# qinxie.net
KiCad netlist of a schematic drawn in Altium Designer
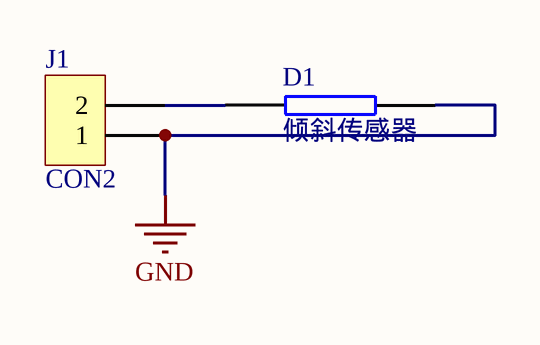
[diagram p0: qinxie.SchDoc]

(export (version "E")
  (design (tool "Eeschema 10.0.6"))
  (components
    (comp (ref "D1") (value "倾斜传感器") (footprint "倾斜传感器") (libsource (lib "AIWAC-bolsterV01") (part "R")))
    (comp (ref "J1")
      (value "CON2")
      (footprint "J-SH1.0-T-1-LT-2A")
      (description "Connector")
      (libsource (lib "AIWAC-bolsterV01") (part "CON2"))
    )
  )
  (nets
    (net (code "1") (name "GND") (class "Default")
      (node (ref "D1") (pin "2") (pinfunction "2_2") (pintype "passive"))
      (node (ref "J1") (pin "1") (pinfunction "1_1") (pintype "passive"))
    )
    (net (code "2") (name "Net-(D1-Pad1)") (class "Default")
      (node (ref "D1") (pin "1") (pinfunction "1_1") (pintype "passive"))
      (node (ref "J1") (pin "2") (pinfunction "2_2") (pintype "passive"))
    )
  )
)
